# PROC010B_SOP_Headers_Reference.net
KiCad netlist of a schematic drawn in Altium Designer
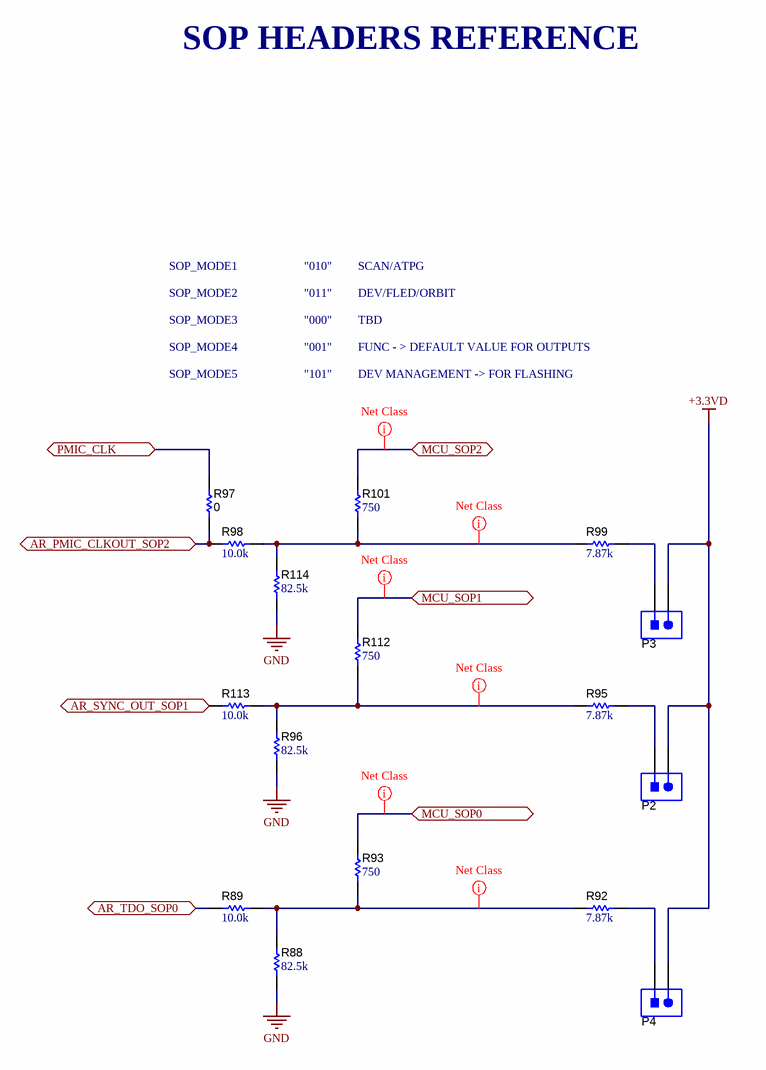
[diagram p0: PROC010B_SOP_Headers_Reference.SchDoc]

(export (version "E")
  (design (tool "Eeschema 10.0.6"))
  (components
    (comp (ref "P2")
      (value "TSW-102-07-G-S")
      (footprint "TSW-102-07-G-S")
      (description "Header, 100mil, 2x1, Gold, TH")
      (fields (field (name "MANUFACTURER") "Samtec"))
      (libsource (lib "Altium Vault - TI") (part "CMP-0075405-2"))
    )
    (comp (ref "P3")
      (value "TSW-102-07-G-S")
      (footprint "TSW-102-07-G-S")
      (description "Header, 100mil, 2x1, Gold, TH")
      (fields (field (name "MANUFACTURER") "Samtec"))
      (libsource (lib "Altium Vault - TI") (part "CMP-0075405-2"))
    )
    (comp (ref "P4")
      (value "TSW-102-07-G-S")
      (footprint "TSW-102-07-G-S")
      (description "Header, 100mil, 2x1, Gold, TH")
      (fields (field (name "MANUFACTURER") "Samtec"))
      (libsource (lib "Altium Vault - TI") (part "CMP-0075405-2"))
    )
    (comp (ref "R88")
      (value "CRCW040282K5FKED")
      (footprint "0402L")
      (description "RES, 82.5 k, 1%, 0.063 W, AEC-Q200 Grade 0, 0402")
      (fields (field (name "MANUFACTURER") "Vishay-Dale") (field (name "VALUEDISPLAYED") "82.5k"))
      (libsource (lib "Altium Vault - TI") (part "Resistor"))
    )
    (comp (ref "R89")
      (value "CRCW040210K0FKED")
      (footprint "0402L")
      (description "RES, 10.0 k, 1%, 0.063 W, AEC-Q200 Grade 0, 0402")
      (fields (field (name "MANUFACTURER") "Vishay-Dale") (field (name "VALUEDISPLAYED") "10.0k"))
      (libsource (lib "Altium Vault - TI") (part "CMP-0025958-3"))
    )
    (comp (ref "R92")
      (value "CRCW04027K87FKED")
      (footprint "0402L")
      (description "RES, 7.87 k, 1%, 0.063 W, AEC-Q200 Grade 0, 0402")
      (fields (field (name "MANUFACTURER") "Vishay-Dale") (field (name "VALUEDISPLAYED") "7.87k"))
      (libsource (lib "Altium Vault - TI") (part "Resistor"))
    )
    (comp (ref "R93")
      (value "CRCW0402750RFKED")
      (footprint "0402L")
      (description "RES, 750, 1%, 0.063 W, AEC-Q200 Grade 0, 0402")
      (fields (field (name "MANUFACTURER") "Vishay-Dale") (field (name "VALUEDISPLAYED") "750"))
      (libsource (lib "Altium Vault - TI") (part "Resistor"))
    )
    (comp (ref "R95")
      (value "CRCW04027K87FKED")
      (footprint "0402L")
      (description "RES, 7.87 k, 1%, 0.063 W, AEC-Q200 Grade 0, 0402")
      (fields (field (name "MANUFACTURER") "Vishay-Dale") (field (name "VALUEDISPLAYED") "7.87k"))
      (libsource (lib "Altium Vault - TI") (part "Resistor"))
    )
    (comp (ref "R96")
      (value "CRCW040282K5FKED")
      (footprint "0402L")
      (description "RES, 82.5 k, 1%, 0.063 W, AEC-Q200 Grade 0, 0402")
      (fields (field (name "MANUFACTURER") "Vishay-Dale") (field (name "VALUEDISPLAYED") "82.5k"))
      (libsource (lib "Altium Vault - TI") (part "Resistor"))
    )
    (comp (ref "R97")
      (value "ERJ-2GE0R00X")
      (footprint "0402L")
      (description "RES, 0, 5%, 0.063 W, 0402")
      (fields
        (field (name "MANUFACTURER") "Panasonic")
        (field (name "VALUEDISPLAYED") "0")
        (field (name "PUBLISHER") "Texas Instruments")
      )
      (libsource (lib "Altium Vault - TI") (part "CMP-0026992-2"))
    )
    (comp (ref "R98")
      (value "CRCW040210K0FKED")
      (footprint "0402L")
      (description "RES, 10.0 k, 1%, 0.063 W, AEC-Q200 Grade 0, 0402")
      (fields (field (name "MANUFACTURER") "Vishay-Dale") (field (name "VALUEDISPLAYED") "10.0k"))
      (libsource (lib "Altium Vault - TI") (part "CMP-0025958-3"))
    )
    (comp (ref "R99")
      (value "CRCW04027K87FKED")
      (footprint "0402L")
      (description "RES, 7.87 k, 1%, 0.063 W, AEC-Q200 Grade 0, 0402")
      (fields (field (name "MANUFACTURER") "Vishay-Dale") (field (name "VALUEDISPLAYED") "7.87k"))
      (libsource (lib "Altium Vault - TI") (part "Resistor"))
    )
    (comp (ref "R101")
      (value "CRCW0402750RFKED")
      (footprint "0402L")
      (description "RES, 750, 1%, 0.063 W, AEC-Q200 Grade 0, 0402")
      (fields (field (name "MANUFACTURER") "Vishay-Dale") (field (name "VALUEDISPLAYED") "750"))
      (libsource (lib "Altium Vault - TI") (part "CMP-0026542-2"))
    )
    (comp (ref "R112")
      (value "CRCW0402750RFKED")
      (footprint "0402L")
      (description "RES, 750, 1%, 0.063 W, AEC-Q200 Grade 0, 0402")
      (fields (field (name "MANUFACTURER") "Vishay-Dale") (field (name "VALUEDISPLAYED") "750"))
      (libsource (lib "Altium Vault - TI") (part "Resistor"))
    )
    (comp (ref "R113")
      (value "CRCW040210K0FKED")
      (footprint "0402L")
      (description "RES, 10.0 k, 1%, 0.063 W, AEC-Q200 Grade 0, 0402")
      (fields (field (name "MANUFACTURER") "Vishay-Dale") (field (name "VALUEDISPLAYED") "10.0k"))
      (libsource (lib "Altium Vault - TI") (part "CMP-0025958-3"))
    )
    (comp (ref "R114")
      (value "CRCW040282K5FKED")
      (footprint "0402L")
      (description "RES, 82.5 k, 1%, 0.063 W, AEC-Q200 Grade 0, 0402")
      (fields (field (name "MANUFACTURER") "Vishay-Dale") (field (name "VALUEDISPLAYED") "82.5k"))
      (libsource (lib "Altium Vault - TI") (part "CMP-0026574-2"))
    )
  )
  (nets
    (net (code "1") (name "+3.3VD") (class "Default")
      (node (ref "P2") (pin "2") (pinfunction "2_2") (pintype "passive"))
      (node (ref "P3") (pin "2") (pinfunction "2_2") (pintype "passive"))
      (node (ref "P4") (pin "2") (pinfunction "2_2") (pintype "passive"))
    )
    (net (code "2") (name "/AR_PMIC_CLKOUT_SOP2") (class "Default")
      (node (ref "R97") (pin "1") (pinfunction "1_1") (pintype "passive"))
      (node (ref "R98") (pin "1") (pinfunction "1_1") (pintype "passive"))
    )
    (net (code "3") (name "/AR_SYNC_OUT_SOP1") (class "Default")
      (node (ref "R113") (pin "1") (pinfunction "1_1") (pintype "passive"))
    )
    (net (code "4") (name "/AR_TDO_SOP0") (class "Default")
      (node (ref "R89") (pin "1") (pinfunction "1_1") (pintype "passive"))
    )
    (net (code "5") (name "/MCU_SOP0") (class "Default")
      (node (ref "R93") (pin "2") (pinfunction "2_2") (pintype "passive"))
    )
    (net (code "6") (name "/MCU_SOP1") (class "Default")
      (node (ref "R112") (pin "2") (pinfunction "2_2") (pintype "passive"))
    )
    (net (code "7") (name "/MCU_SOP2") (class "Default")
      (node (ref "R101") (pin "2") (pinfunction "2_2") (pintype "passive"))
    )
    (net (code "8") (name "/PMIC_CLK") (class "Default")
      (node (ref "R97") (pin "2") (pinfunction "2_2") (pintype "passive"))
    )
    (net (code "9") (name "GND") (class "Default")
      (node (ref "R114") (pin "1") (pinfunction "1_1") (pintype "passive"))
      (node (ref "R88") (pin "1") (pinfunction "1_1") (pintype "passive"))
      (node (ref "R96") (pin "1") (pinfunction "1_1") (pintype "passive"))
    )
    (net (code "10") (name "Net-(P2-Pad1)") (class "Default")
      (node (ref "P2") (pin "1") (pinfunction "1_1") (pintype "passive"))
      (node (ref "R95") (pin "2") (pinfunction "2_2") (pintype "passive"))
    )
    (net (code "11") (name "Net-(P3-Pad1)") (class "Default")
      (node (ref "P3") (pin "1") (pinfunction "1_1") (pintype "passive"))
      (node (ref "R99") (pin "2") (pinfunction "2_2") (pintype "passive"))
    )
    (net (code "12") (name "Net-(P4-Pad1)") (class "Default")
      (node (ref "P4") (pin "1") (pinfunction "1_1") (pintype "passive"))
      (node (ref "R92") (pin "2") (pinfunction "2_2") (pintype "passive"))
    )
    (net (code "13") (name "Net-(R88-Pad2)") (class "Default")
      (node (ref "R88") (pin "2") (pinfunction "2_2") (pintype "passive"))
      (node (ref "R89") (pin "2") (pinfunction "2_2") (pintype "passive"))
      (node (ref "R92") (pin "1") (pinfunction "1_1") (pintype "passive"))
      (node (ref "R93") (pin "1") (pinfunction "1_1") (pintype "passive"))
    )
    (net (code "14") (name "Net-(R101-Pad1)") (class "Default")
      (node (ref "R101") (pin "1") (pinfunction "1_1") (pintype "passive"))
      (node (ref "R114") (pin "2") (pinfunction "2_2") (pintype "passive"))
      (node (ref "R98") (pin "2") (pinfunction "2_2") (pintype "passive"))
      (node (ref "R99") (pin "1") (pinfunction "1_1") (pintype "passive"))
    )
    (net (code "15") (name "Net-(R112-Pad1)") (class "Default")
      (node (ref "R112") (pin "1") (pinfunction "1_1") (pintype "passive"))
      (node (ref "R113") (pin "2") (pinfunction "2_2") (pintype "passive"))
      (node (ref "R95") (pin "1") (pinfunction "1_1") (pintype "passive"))
      (node (ref "R96") (pin "2") (pinfunction "2_2") (pintype "passive"))
    )
  )
)
